# Microcontroller_Schematic.net
KiCad netlist of a schematic drawn in Altium Designer
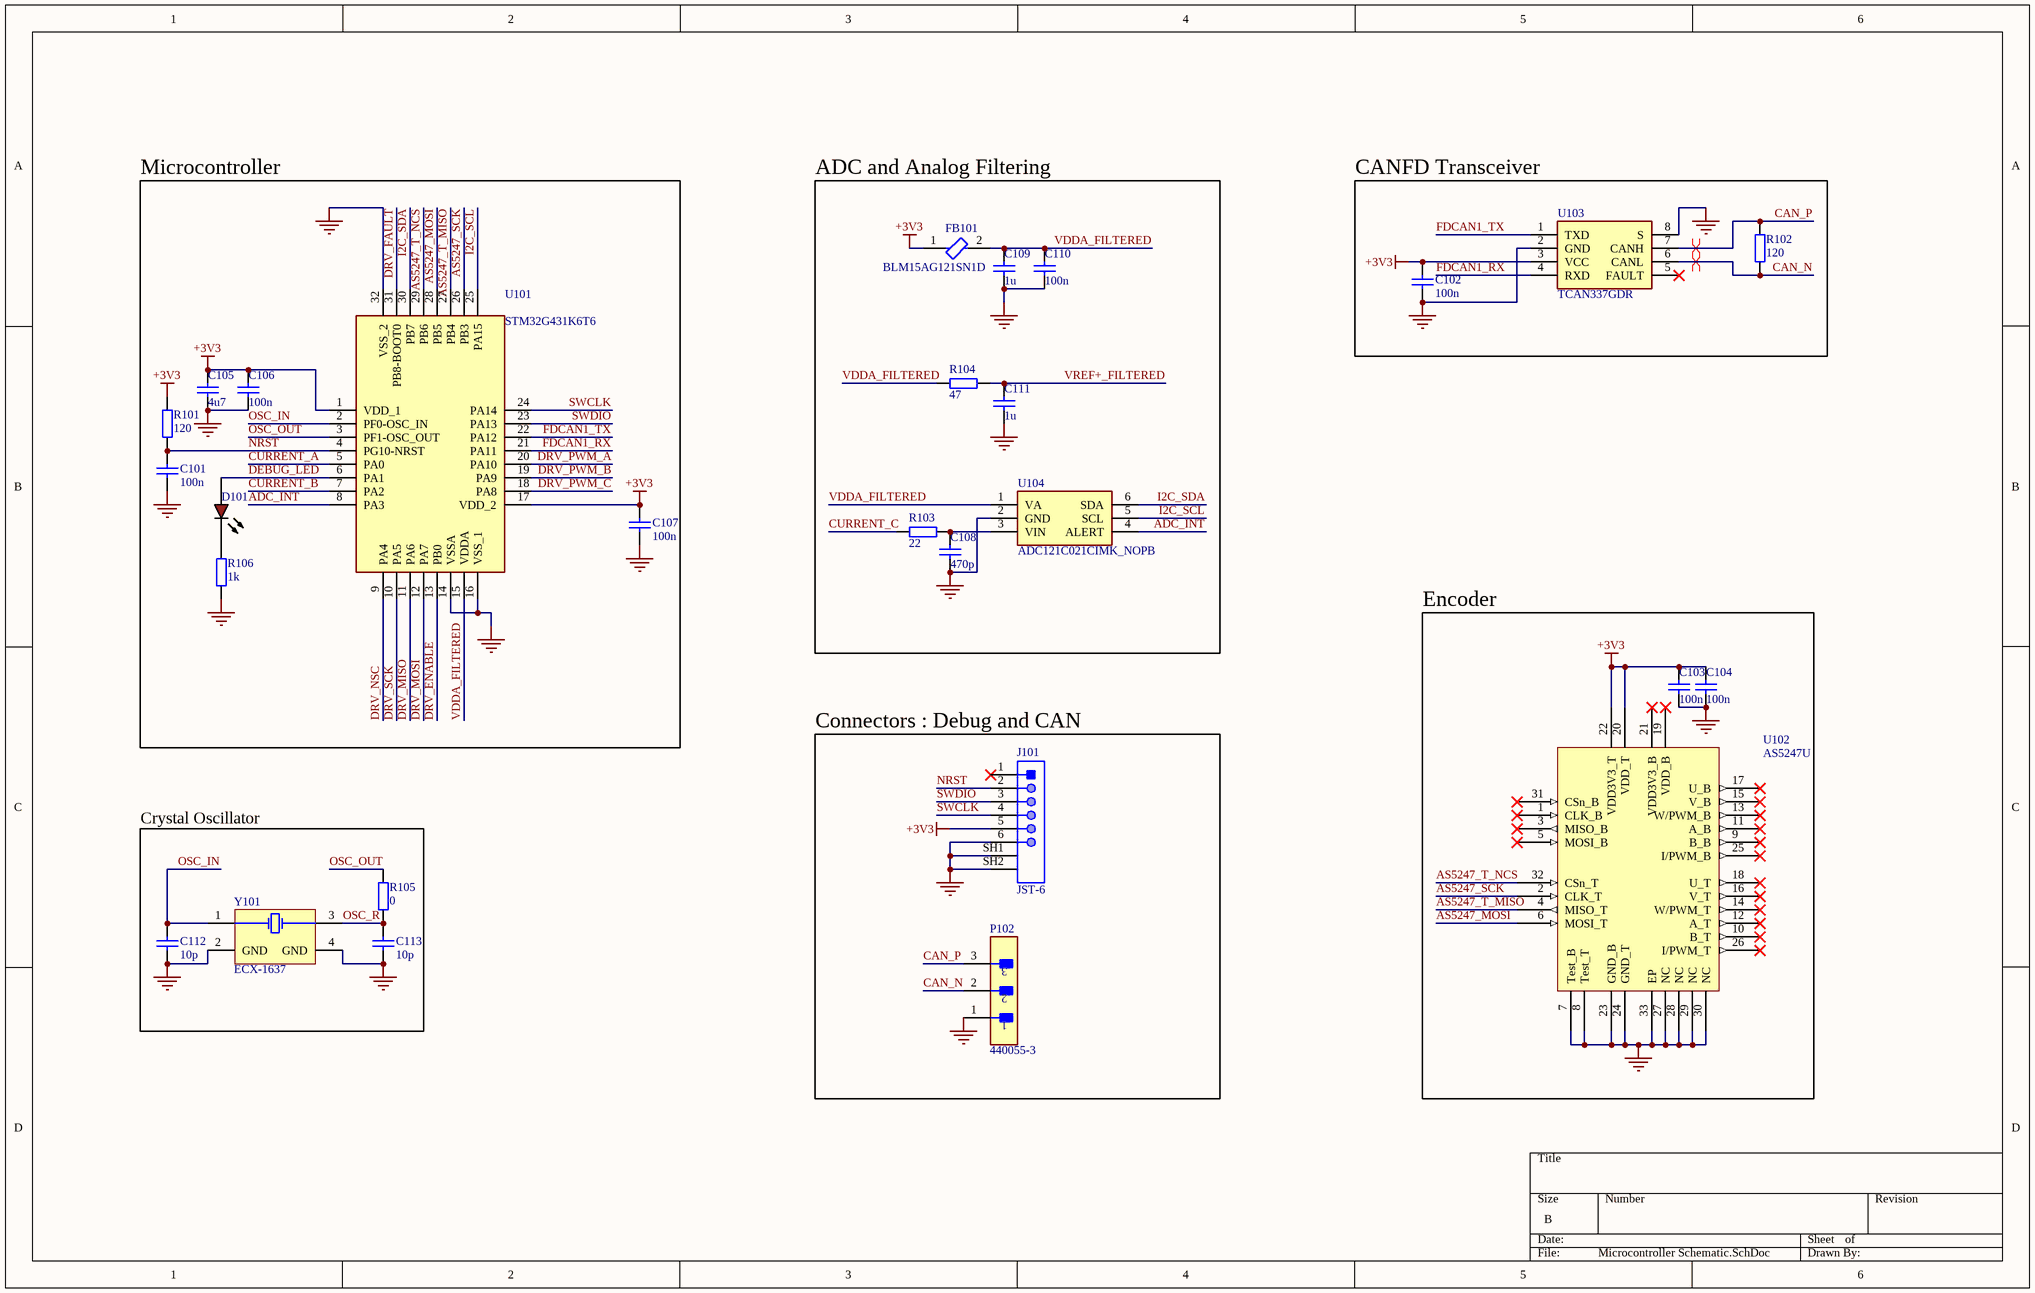
[diagram p0: Microcontroller Schematic.SchDoc]

(export (version "E")
  (design (tool "Eeschema 10.0.6"))
  (components
    (comp (ref "C101")
      (value "100n")
      (footprint "FootprintLib:CAPC1005X55N")
      (description "Capacitor")
      (fields
        (field (name "MANUFACTURER_PART_NUMBER") "CL05B104KO5NNNC")
        (field (name "MOUSER PART NUMBER") "187-CL05B104KO5NNNC")
      )
      (libsource (lib "SymbolLib") (part "CAP_0402_16V"))
    )
    (comp (ref "C102")
      (value "100n")
      (footprint "FootprintLib:CAPC1005X55N")
      (description "Capacitor")
      (fields
        (field (name "MANUFACTURER_PART_NUMBER") "CL05B104KO5NNNC")
        (field (name "MOUSER PART NUMBER") "187-CL05B104KO5NNNC")
      )
      (libsource (lib "SymbolLib") (part "CAP_0402_16V"))
    )
    (comp (ref "C103")
      (value "100n")
      (footprint "FootprintLib:CAPC1005X55N")
      (description "Capacitor")
      (fields
        (field (name "MANUFACTURER_PART_NUMBER") "CL05B104KO5NNNC")
        (field (name "MOUSER PART NUMBER") "187-CL05B104KO5NNNC")
      )
      (libsource (lib "SymbolLib") (part "CAP_0402_16V"))
    )
    (comp (ref "C104")
      (value "100n")
      (footprint "FootprintLib:CAPC1005X55N")
      (description "Capacitor")
      (fields
        (field (name "MANUFACTURER_PART_NUMBER") "CL05B104KO5NNNC")
        (field (name "MOUSER PART NUMBER") "187-CL05B104KO5NNNC")
      )
      (libsource (lib "SymbolLib") (part "CAP_0402_16V"))
    )
    (comp (ref "C105")
      (value "4u7")
      (footprint "FootprintLib:CAPC1608X90N")
      (description "Capacitor")
      (fields
        (field (name "MANUFACTURER_PART_NUMBER") "CL05B104KO5NNNC")
        (field (name "MOUSER PART NUMBER") "187-CL05B104KO5NNNC")
      )
      (libsource (lib "SymbolLib") (part "CAP_0603_16V"))
    )
    (comp (ref "C106")
      (value "100n")
      (footprint "FootprintLib:CAPC1005X55N")
      (description "Capacitor")
      (fields
        (field (name "MANUFACTURER_PART_NUMBER") "CL05B104KO5NNNC")
        (field (name "MOUSER PART NUMBER") "187-CL05B104KO5NNNC")
      )
      (libsource (lib "SymbolLib") (part "CAP_0402_16V"))
    )
    (comp (ref "C107")
      (value "100n")
      (footprint "FootprintLib:CAPC1005X55N")
      (description "Capacitor")
      (fields
        (field (name "MANUFACTURER_PART_NUMBER") "CL05B104KO5NNNC")
        (field (name "MOUSER PART NUMBER") "187-CL05B104KO5NNNC")
      )
      (libsource (lib "SymbolLib") (part "CAP_0402_16V"))
    )
    (comp (ref "C108")
      (value "470p")
      (footprint "FootprintLib:CAPC1005X55N")
      (description "Capacitor")
      (fields
        (field (name "MANUFACTURER_PART_NUMBER") "CL05B104KO5NNNC")
        (field (name "MOUSER PART NUMBER") "187-CL05B104KO5NNNC")
      )
      (libsource (lib "SymbolLib") (part "CAP_0402_16V"))
    )
    (comp (ref "C109")
      (value "1u")
      (footprint "FootprintLib:CAPC1005X55N")
      (description "Capacitor")
      (fields
        (field (name "MANUFACTURER_PART_NUMBER") "CL05B104KO5NNNC")
        (field (name "MOUSER PART NUMBER") "187-CL05B104KO5NNNC")
      )
      (libsource (lib "SymbolLib") (part "CAP_0402_16V"))
    )
    (comp (ref "C110")
      (value "100n")
      (footprint "FootprintLib:CAPC1005X55N")
      (description "Capacitor")
      (fields
        (field (name "MANUFACTURER_PART_NUMBER") "CL05B104KO5NNNC")
        (field (name "MOUSER PART NUMBER") "187-CL05B104KO5NNNC")
      )
      (libsource (lib "SymbolLib") (part "CAP_0402_16V"))
    )
    (comp (ref "C111")
      (value "1u")
      (footprint "FootprintLib:CAPC1005X55N")
      (description "Capacitor")
      (fields
        (field (name "MANUFACTURER_PART_NUMBER") "CL05B104KO5NNNC")
        (field (name "MOUSER PART NUMBER") "187-CL05B104KO5NNNC")
      )
      (libsource (lib "SymbolLib") (part "CAP_0402_16V"))
    )
    (comp (ref "C112")
      (value "10p")
      (footprint "FootprintLib:CAPC1005X55N")
      (description "Capacitor")
      (fields
        (field (name "MANUFACTURER_PART_NUMBER") "CL05B104KO5NNNC")
        (field (name "MOUSER PART NUMBER") "187-CL05B104KO5NNNC")
      )
      (libsource (lib "SymbolLib") (part "CAP_0402_16V"))
    )
    (comp (ref "C113")
      (value "10p")
      (footprint "FootprintLib:CAPC1005X55N")
      (description "Capacitor")
      (fields
        (field (name "MANUFACTURER_PART_NUMBER") "CL05B104KO5NNNC")
        (field (name "MOUSER PART NUMBER") "187-CL05B104KO5NNNC")
      )
      (libsource (lib "SymbolLib") (part "CAP_0402_16V"))
    )
    (comp (ref "D101")
      (value "RED")
      (footprint "150040GS73220")
      (libsource (lib "SymbolLib") (part "RED_0402_LED"))
    )
    (comp (ref "FB101")
      (value "BLM15AG121SN1D")
      (footprint "FP-BLM15-0_05-MFG")
      (description "Chip Ferrite Bead, 0402, 120Ω @ 100MHz, 0.19Ω, 25%, 550mA")
      (fields (field (name "TOLERANCE") "25%"))
      (libsource (lib "Altium Content Vault") (part "5f30dd21d616792df468990f7003faa"))
    )
    (comp (ref "J101")
      (value "JST-6")
      (footprint "JST_S6B-ZR-SM4A-TF(LF)(SN)")
      (libsource (lib "SymbolLib") (part "JST-6"))
    )
    (comp (ref "P102")
      (value "440055-3")
      (footprint "FP-440055-3-MFG")
      (description "CONN HEADER R/A 3POS 2MM")
      (fields
        (field (name "MANUFACTURER") "TE Connectivity")
        (field (name "OCTOPART") "https://octopart.com/440055-3-te+connectivity-40644627")
      )
      (libsource (lib "Altium Content Vault") (part "0d3f023dd272f625e17a2be33dea85f"))
    )
    (comp (ref "R101")
      (value "120")
      (footprint "FootprintLib:RESC1005X40N")
      (libsource (lib "SymbolLib") (part "RES_0402"))
    )
    (comp (ref "R102")
      (value "120")
      (footprint "FootprintLib:RESC1005X40N")
      (libsource (lib "SymbolLib") (part "RES_0402"))
    )
    (comp (ref "R103")
      (value "22")
      (footprint "FootprintLib:RESC1005X40N")
      (libsource (lib "SymbolLib") (part "RES_0402"))
    )
    (comp (ref "R104")
      (value "47")
      (footprint "FootprintLib:RESC1005X40N")
      (libsource (lib "SymbolLib") (part "RES_0402"))
    )
    (comp (ref "R105")
      (value "0")
      (footprint "FootprintLib:RESC1005X40N")
      (libsource (lib "SymbolLib") (part "RES_0402"))
    )
    (comp (ref "R106")
      (value "1k")
      (footprint "FootprintLib:RESC1005X40N")
      (libsource (lib "SymbolLib") (part "RES_0402"))
    )
    (comp (ref "U101")
      (value "STM32G431K6T6")
      (footprint "QFP80P900X900X160-32N")
      (libsource (lib "SymbolLib") (part "STM32G431K6T6"))
    )
    (comp (ref "U102")
      (value "AS5247U")
      (footprint "QFN-N32-THM")
      (description "ams AS5247U Magnetic Rotary Position Sensor")
      (libsource (lib "SymbolLib") (part "AS5247U"))
    )
    (comp (ref "U103")
      (value "TCAN337GDR")
      (footprint "SamacSys:SOIC127P600X175-8N")
      (description "Integrated Circuit")
      (fields (field (name "MOUSER PART NUMBER") "595-TCAN337GDR"))
      (libsource (lib "*") (part "TCAN337GDR"))
    )
    (comp (ref "U104")
      (value "ADC121C021CIMK_NOPB")
      (footprint "FootprintLib:SOT95P280X110-6N")
      (description "Integrated Circuit")
      (fields
        (field (name "MANUFACTURER_PART_NUMBER") "ADC121C021CIMK/NOPB")
        (field (name "MOUSER PART NUMBER") "926-AD121C021CIMKNPB")
      )
      (libsource (lib "SymbolLib") (part "ADC121C021CIMK_NOPB"))
    )
    (comp (ref "Y101")
      (value "ECX-1637")
      (footprint "ECX-1637")
      (libsource (lib "SymbolLib") (part "ECX-1637"))
    )
  )
  (nets
    (net (code "1") (name "+3V3") (class "Default")
      (node (ref "C102") (pin "2") (pinfunction "2_2") (pintype "passive"))
      (node (ref "C103") (pin "2") (pinfunction "2_2") (pintype "passive"))
      (node (ref "C104") (pin "2") (pinfunction "2_2") (pintype "passive"))
      (node (ref "C105") (pin "1") (pinfunction "1_1") (pintype "passive"))
      (node (ref "C106") (pin "2") (pinfunction "2_2") (pintype "passive"))
      (node (ref "C107") (pin "2") (pinfunction "2_2") (pintype "passive"))
      (node (ref "FB101") (pin "1") (pinfunction "1_1") (pintype "passive"))
      (node (ref "J101") (pin "5") (pinfunction "5_5") (pintype "passive"))
      (node (ref "R101") (pin "1") (pinfunction "1_1") (pintype "passive"))
      (node (ref "U101") (pin "1") (pinfunction "VDD_1_1") (pintype "passive"))
      (node (ref "U101") (pin "17") (pinfunction "VDD_2_17") (pintype "passive"))
      (node (ref "U102") (pin "20") (pinfunction "VDD_T_20") (pintype "power_in"))
      (node (ref "U102") (pin "22") (pinfunction "VDD3V3_T_22") (pintype "power_in"))
      (node (ref "U103") (pin "3") (pinfunction "VCC_3") (pintype "passive"))
    )
    (net (code "2") (name "/ADC_INT") (class "Default")
      (node (ref "U101") (pin "8") (pinfunction "PA3_8") (pintype "passive"))
      (node (ref "U104") (pin "4") (pinfunction "ALERT_4") (pintype "passive"))
    )
    (net (code "3") (name "/AS5247_MOSI") (class "Default")
      (node (ref "U101") (pin "28") (pinfunction "PB5_28") (pintype "passive"))
      (node (ref "U102") (pin "6") (pinfunction "MOSI_T_6") (pintype "input"))
    )
    (net (code "4") (name "/AS5247_SCK") (class "Default")
      (node (ref "U101") (pin "26") (pinfunction "PB3_26") (pintype "passive"))
      (node (ref "U102") (pin "2") (pinfunction "CLK_T_2") (pintype "input"))
    )
    (net (code "5") (name "/AS5247_T_MISO") (class "Default")
      (node (ref "U101") (pin "27") (pinfunction "PB4_27") (pintype "passive"))
      (node (ref "U102") (pin "4") (pinfunction "MISO_T_4") (pintype "output"))
    )
    (net (code "6") (name "/AS5247_T_NCS") (class "Default")
      (node (ref "U101") (pin "29") (pinfunction "PB6_29") (pintype "passive"))
      (node (ref "U102") (pin "32") (pinfunction "CSn_T_32") (pintype "input"))
    )
    (net (code "7") (name "/CAN_N") (class "Default")
      (node (ref "P102") (pin "2") (pinfunction "2_2") (pintype "passive"))
      (node (ref "R102") (pin "1") (pinfunction "1_1") (pintype "passive"))
      (node (ref "U103") (pin "6") (pinfunction "CANL_6") (pintype "passive"))
    )
    (net (code "8") (name "/CAN_P") (class "Default")
      (node (ref "P102") (pin "3") (pinfunction "3_3") (pintype "passive"))
      (node (ref "R102") (pin "2") (pinfunction "2_2") (pintype "passive"))
      (node (ref "U103") (pin "7") (pinfunction "CANH_7") (pintype "passive"))
    )
    (net (code "9") (name "/CURRENT_A") (class "Default")
      (node (ref "U101") (pin "5") (pinfunction "PA0_5") (pintype "passive"))
    )
    (net (code "10") (name "/CURRENT_B") (class "Default")
      (node (ref "U101") (pin "7") (pinfunction "PA2_7") (pintype "passive"))
    )
    (net (code "11") (name "/CURRENT_C") (class "Default")
      (node (ref "R103") (pin "1") (pinfunction "1_1") (pintype "passive"))
    )
    (net (code "12") (name "/DEBUG_LED") (class "Default")
      (node (ref "D101") (pin "1") (pinfunction "A_1") (pintype "passive"))
      (node (ref "U101") (pin "6") (pinfunction "PA1_6") (pintype "passive"))
    )
    (net (code "13") (name "/DRV_ENABLE") (class "Default")
      (node (ref "U101") (pin "13") (pinfunction "PB0_13") (pintype "passive"))
    )
    (net (code "14") (name "/DRV_FAULT") (class "Default")
      (node (ref "U101") (pin "31") (pinfunction "PB8-BOOT0_31") (pintype "passive"))
    )
    (net (code "15") (name "/DRV_MISO") (class "Default")
      (node (ref "U101") (pin "11") (pinfunction "PA6_11") (pintype "passive"))
    )
    (net (code "16") (name "/DRV_MOSI") (class "Default")
      (node (ref "U101") (pin "12") (pinfunction "PA7_12") (pintype "passive"))
    )
    (net (code "17") (name "/DRV_NSC") (class "Default")
      (node (ref "U101") (pin "9") (pinfunction "PA4_9") (pintype "passive"))
    )
    (net (code "18") (name "/DRV_PWM_A") (class "Default")
      (node (ref "U101") (pin "20") (pinfunction "PA10_20") (pintype "passive"))
    )
    (net (code "19") (name "/DRV_PWM_B") (class "Default")
      (node (ref "U101") (pin "19") (pinfunction "PA9_19") (pintype "passive"))
    )
    (net (code "20") (name "/DRV_PWM_C") (class "Default")
      (node (ref "U101") (pin "18") (pinfunction "PA8_18") (pintype "passive"))
    )
    (net (code "21") (name "/DRV_SCK") (class "Default")
      (node (ref "U101") (pin "10") (pinfunction "PA5_10") (pintype "passive"))
    )
    (net (code "22") (name "/FDCAN1_RX") (class "Default")
      (node (ref "U101") (pin "21") (pinfunction "PA11_21") (pintype "passive"))
      (node (ref "U103") (pin "4") (pinfunction "RXD_4") (pintype "passive"))
    )
    (net (code "23") (name "/FDCAN1_TX") (class "Default")
      (node (ref "U101") (pin "22") (pinfunction "PA12_22") (pintype "passive"))
      (node (ref "U103") (pin "1") (pinfunction "TXD_1") (pintype "passive"))
    )
    (net (code "24") (name "/I2C_SCL") (class "Default")
      (node (ref "U101") (pin "25") (pinfunction "PA15_25") (pintype "passive"))
      (node (ref "U104") (pin "5") (pinfunction "SCL_5") (pintype "passive"))
    )
    (net (code "25") (name "/I2C_SDA") (class "Default")
      (node (ref "U101") (pin "30") (pinfunction "PB7_30") (pintype "passive"))
      (node (ref "U104") (pin "6") (pinfunction "SDA_6") (pintype "passive"))
    )
    (net (code "26") (name "/NRST") (class "Default")
      (node (ref "C101") (pin "1") (pinfunction "1_1") (pintype "passive"))
      (node (ref "J101") (pin "2") (pinfunction "2_2") (pintype "passive"))
      (node (ref "R101") (pin "2") (pinfunction "2_2") (pintype "passive"))
      (node (ref "U101") (pin "4") (pinfunction "PG10-NRST_4") (pintype "passive"))
    )
    (net (code "27") (name "/OSC_IN") (class "Default")
      (node (ref "C112") (pin "2") (pinfunction "2_2") (pintype "passive"))
      (node (ref "U101") (pin "2") (pinfunction "PF0-OSC_IN_2") (pintype "passive"))
      (node (ref "Y101") (pin "1") (pinfunction "X1_1") (pintype "passive"))
    )
    (net (code "28") (name "/OSC_OUT") (class "Default")
      (node (ref "R105") (pin "1") (pinfunction "1_1") (pintype "passive"))
      (node (ref "U101") (pin "3") (pinfunction "PF1-OSC_OUT_3") (pintype "passive"))
    )
    (net (code "29") (name "/OSC_R") (class "Default")
      (node (ref "C113") (pin "2") (pinfunction "2_2") (pintype "passive"))
      (node (ref "R105") (pin "2") (pinfunction "2_2") (pintype "passive"))
      (node (ref "Y101") (pin "3") (pinfunction "X2_3") (pintype "passive"))
    )
    (net (code "30") (name "/SWCLK") (class "Default")
      (node (ref "J101") (pin "4") (pinfunction "4_4") (pintype "passive"))
      (node (ref "U101") (pin "24") (pinfunction "PA14_24") (pintype "passive"))
    )
    (net (code "31") (name "/SWDIO") (class "Default")
      (node (ref "J101") (pin "3") (pinfunction "3_3") (pintype "passive"))
      (node (ref "U101") (pin "23") (pinfunction "PA13_23") (pintype "passive"))
    )
    (net (code "32") (name "/VDDA_FILTERED") (class "Default")
      (node (ref "C109") (pin "2") (pinfunction "2_2") (pintype "passive"))
      (node (ref "C110") (pin "2") (pinfunction "2_2") (pintype "passive"))
      (node (ref "FB101") (pin "2") (pinfunction "2_2") (pintype "passive"))
      (node (ref "R104") (pin "1") (pinfunction "1_1") (pintype "passive"))
      (node (ref "U101") (pin "15") (pinfunction "VDDA_15") (pintype "passive"))
      (node (ref "U104") (pin "1") (pinfunction "VA_1") (pintype "passive"))
    )
    (net (code "33") (name "/VREF+_FILTERED") (class "Default")
      (node (ref "C111") (pin "2") (pinfunction "2_2") (pintype "passive"))
      (node (ref "R104") (pin "2") (pinfunction "2_2") (pintype "passive"))
    )
    (net (code "34") (name "GND") (class "Default")
      (node (ref "C101") (pin "2") (pinfunction "2_2") (pintype "passive"))
      (node (ref "C102") (pin "1") (pinfunction "1_1") (pintype "passive"))
      (node (ref "C103") (pin "1") (pinfunction "1_1") (pintype "passive"))
      (node (ref "C104") (pin "1") (pinfunction "1_1") (pintype "passive"))
      (node (ref "C105") (pin "2") (pinfunction "2_2") (pintype "passive"))
      (node (ref "C106") (pin "1") (pinfunction "1_1") (pintype "passive"))
      (node (ref "C107") (pin "1") (pinfunction "1_1") (pintype "passive"))
      (node (ref "C108") (pin "1") (pinfunction "1_1") (pintype "passive"))
      (node (ref "C109") (pin "1") (pinfunction "1_1") (pintype "passive"))
      (node (ref "C110") (pin "1") (pinfunction "1_1") (pintype "passive"))
      (node (ref "C111") (pin "1") (pinfunction "1_1") (pintype "passive"))
      (node (ref "C112") (pin "1") (pinfunction "1_1") (pintype "passive"))
      (node (ref "C113") (pin "1") (pinfunction "1_1") (pintype "passive"))
      (node (ref "J101") (pin "6") (pinfunction "6_6") (pintype "passive"))
      (node (ref "J101") (pin "SH1") (pinfunction "SH1_SH1") (pintype "passive"))
      (node (ref "J101") (pin "SH2") (pinfunction "SH2_SH2") (pintype "passive"))
      (node (ref "P102") (pin "1") (pinfunction "1_1") (pintype "passive"))
      (node (ref "R106") (pin "2") (pinfunction "2_2") (pintype "passive"))
      (node (ref "U101") (pin "14") (pinfunction "VSSA_14") (pintype "passive"))
      (node (ref "U101") (pin "16") (pinfunction "VSS_1_16") (pintype "passive"))
      (node (ref "U101") (pin "32") (pinfunction "VSS_2_32") (pintype "passive"))
      (node (ref "U102") (pin "23") (pinfunction "GND_B_23") (pintype "power_in"))
      (node (ref "U102") (pin "24") (pinfunction "GND_T_24") (pintype "power_in"))
      (node (ref "U102") (pin "27") (pinfunction "NC_27") (pintype "passive"))
      (node (ref "U102") (pin "28") (pinfunction "NC_28") (pintype "passive"))
      (node (ref "U102") (pin "29") (pinfunction "NC_29") (pintype "passive"))
      (node (ref "U102") (pin "30") (pinfunction "NC_30") (pintype "passive"))
      (node (ref "U102") (pin "33") (pinfunction "EP_33") (pintype "passive"))
      (node (ref "U102") (pin "7") (pinfunction "Test_B_7") (pintype "power_in"))
      (node (ref "U102") (pin "8") (pinfunction "Test_T_8") (pintype "power_in"))
      (node (ref "U103") (pin "2") (pinfunction "GND_2") (pintype "passive"))
      (node (ref "U103") (pin "8") (pinfunction "S_8") (pintype "passive"))
      (node (ref "U104") (pin "2") (pinfunction "GND_2") (pintype "passive"))
      (node (ref "Y101") (pin "2") (pinfunction "GND_2") (pintype "power_in"))
      (node (ref "Y101") (pin "4") (pinfunction "GND_4") (pintype "power_in"))
    )
    (net (code "35") (name "Net-(D101-K)") (class "Default")
      (node (ref "D101") (pin "2") (pinfunction "K_2") (pintype "passive"))
      (node (ref "R106") (pin "1") (pinfunction "1_1") (pintype "passive"))
    )
    (net (code "36") (name "Net-(U104-VIN)") (class "Default")
      (node (ref "C108") (pin "2") (pinfunction "2_2") (pintype "passive"))
      (node (ref "R103") (pin "2") (pinfunction "2_2") (pintype "passive"))
      (node (ref "U104") (pin "3") (pinfunction "VIN_3") (pintype "passive"))
    )
    (net (code "37") (name "unconnected-(J101-Pad1)") (class "Default")
      (node (ref "J101") (pin "1") (pinfunction "1_1") (pintype "passive+no_connect"))
    )
    (net (code "38") (name "unconnected-(U102-A_B-Pad11)") (class "Default")
      (node (ref "U102") (pin "11") (pinfunction "A_B_11") (pintype "output+no_connect"))
    )
    (net (code "39") (name "unconnected-(U102-A_T-Pad12)") (class "Default")
      (node (ref "U102") (pin "12") (pinfunction "A_T_12") (pintype "output+no_connect"))
    )
    (net (code "40") (name "unconnected-(U102-B_B-Pad9)") (class "Default")
      (node (ref "U102") (pin "9") (pinfunction "B_B_9") (pintype "output+no_connect"))
    )
    (net (code "41") (name "unconnected-(U102-B_T-Pad10)") (class "Default")
      (node (ref "U102") (pin "10") (pinfunction "B_T_10") (pintype "output+no_connect"))
    )
    (net (code "42") (name "unconnected-(U102-CLK_B-Pad1)") (class "Default")
      (node (ref "U102") (pin "1") (pinfunction "CLK_B_1") (pintype "input+no_connect"))
    )
    (net (code "43") (name "unconnected-(U102-CSn_B-Pad31)") (class "Default")
      (node (ref "U102") (pin "31") (pinfunction "CSn_B_31") (pintype "input+no_connect"))
    )
    (net (code "44") (name "unconnected-(U102-I{slash}PWM_B-Pad25)") (class "Default")
      (node (ref "U102") (pin "25") (pinfunction "I/PWM_B_25") (pintype "output+no_connect"))
    )
    (net (code "45") (name "unconnected-(U102-I{slash}PWM_T-Pad26)") (class "Default")
      (node (ref "U102") (pin "26") (pinfunction "I/PWM_T_26") (pintype "output+no_connect"))
    )
    (net (code "46") (name "unconnected-(U102-MISO_B-Pad3)") (class "Default")
      (node (ref "U102") (pin "3") (pinfunction "MISO_B_3") (pintype "output+no_connect"))
    )
    (net (code "47") (name "unconnected-(U102-MOSI_B-Pad5)") (class "Default")
      (node (ref "U102") (pin "5") (pinfunction "MOSI_B_5") (pintype "input+no_connect"))
    )
    (net (code "48") (name "unconnected-(U102-U_B-Pad17)") (class "Default")
      (node (ref "U102") (pin "17") (pinfunction "U_B_17") (pintype "output+no_connect"))
    )
    (net (code "49") (name "unconnected-(U102-U_T-Pad18)") (class "Default")
      (node (ref "U102") (pin "18") (pinfunction "U_T_18") (pintype "output+no_connect"))
    )
    (net (code "50") (name "unconnected-(U102-VDD3V3_B-Pad21)") (class "Default")
      (node (ref "U102") (pin "21") (pinfunction "VDD3V3_B_21") (pintype "power_in+no_connect"))
    )
    (net (code "51") (name "unconnected-(U102-VDD_B-Pad19)") (class "Default")
      (node (ref "U102") (pin "19") (pinfunction "VDD_B_19") (pintype "power_in+no_connect"))
    )
    (net (code "52") (name "unconnected-(U102-V_B-Pad15)") (class "Default")
      (node (ref "U102") (pin "15") (pinfunction "V_B_15") (pintype "output+no_connect"))
    )
    (net (code "53") (name "unconnected-(U102-V_T-Pad16)") (class "Default")
      (node (ref "U102") (pin "16") (pinfunction "V_T_16") (pintype "output+no_connect"))
    )
    (net (code "54") (name "unconnected-(U102-W{slash}PWM_B-Pad13)") (class "Default")
      (node (ref "U102") (pin "13") (pinfunction "W/PWM_B_13") (pintype "output+no_connect"))
    )
    (net (code "55") (name "unconnected-(U102-W{slash}PWM_T-Pad14)") (class "Default")
      (node (ref "U102") (pin "14") (pinfunction "W/PWM_T_14") (pintype "output+no_connect"))
    )
    (net (code "56") (name "unconnected-(U103-FAULT-Pad5)") (class "Default")
      (node (ref "U103") (pin "5") (pinfunction "FAULT_5") (pintype "passive+no_connect"))
    )
  )
)
